# ESC_Board_Sample.net
KiCad netlist of a schematic drawn in Altium Designer
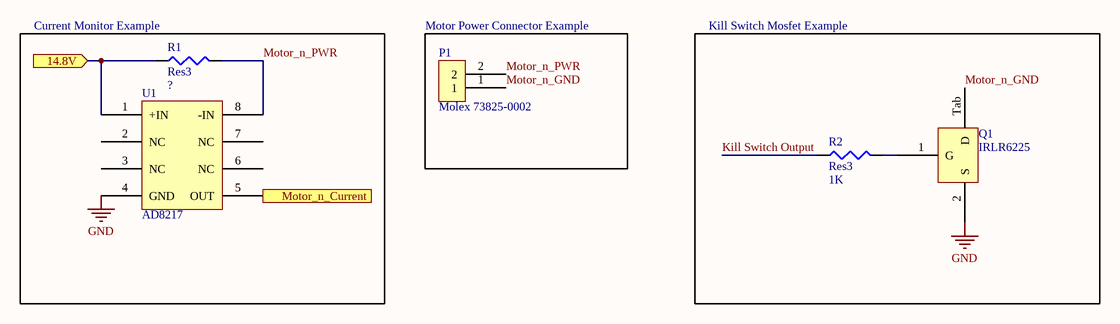
[diagram p0: ESC Board Sample.SchDoc]

(export (version "E")
  (design (tool "Eeschema 10.0.6"))
  (components
    (comp (ref "P1")
      (value "Molex 73825-0002")
      (footprint "Molex 76825-0002")
      (libsource (lib "Molex_Mega_Fit") (part "Molex 73825-0002"))
    )
    (comp (ref "Q1")
      (value "IRLR6225")
      (footprint "IRLR6225")
      (libsource (lib "BaseKillSwitchCircuit") (part "IRLR6225"))
    )
    (comp (ref "R1")
      (value "Res3")
      (footprint "J1-0603")
      (description "Resistor")
      (fields (field (name "ALTIUM_VALUE") "?") (field (name "PUBLISHER") "Altium Limited"))
      (libsource (lib "Miscellaneous Devices") (part "Res3"))
    )
    (comp (ref "R2")
      (value "Res3")
      (footprint "J1-0603")
      (description "Resistor")
      (fields (field (name "ALTIUM_VALUE") "1K") (field (name "PUBLISHER") "Altium Limited"))
      (libsource (lib "BaseKillSwitchCircuit") (part "Res3"))
    )
    (comp (ref "U1")
      (value "AD8217")
      (footprint "AD8217")
      (libsource (lib "BaseCurrentMonitor") (part "AD8217"))
    )
  )
  (nets
    (net (code "1") (name "/14.8V") (class "Default")
      (node (ref "R1") (pin "1") (pinfunction "1_1") (pintype "passive"))
      (node (ref "U1") (pin "1") (pinfunction "+IN_1") (pintype "passive"))
    )
    (net (code "2") (name "/Kill Switch Output") (class "Default")
      (node (ref "R2") (pin "1") (pinfunction "1_1") (pintype "passive"))
    )
    (net (code "3") (name "/Motor_n_Current") (class "Default")
      (node (ref "U1") (pin "5") (pinfunction "OUT_5") (pintype "passive"))
    )
    (net (code "4") (name "/Motor_n_GND") (class "Default")
      (node (ref "P1") (pin "1") (pinfunction "1_1") (pintype "power_in"))
      (node (ref "Q1") (pin "Tab") (pinfunction "D_Tab") (pintype "passive"))
    )
    (net (code "5") (name "/Motor_n_PWR") (class "Default")
      (node (ref "P1") (pin "2") (pinfunction "2_2") (pintype "power_in"))
      (node (ref "R1") (pin "2") (pinfunction "2_2") (pintype "passive"))
      (node (ref "U1") (pin "8") (pinfunction "-IN_8") (pintype "passive"))
    )
    (net (code "6") (name "GND") (class "Default")
      (node (ref "Q1") (pin "2") (pinfunction "S_2") (pintype "passive"))
      (node (ref "U1") (pin "4") (pinfunction "GND_4") (pintype "passive"))
    )
    (net (code "7") (name "Net-(Q1-G)") (class "Default")
      (node (ref "Q1") (pin "1") (pinfunction "G_1") (pintype "passive"))
      (node (ref "R2") (pin "2") (pinfunction "2_2") (pintype "passive"))
    )
    (net (code "8") (name "unconnected-(U1-NC-Pad2)") (class "Default")
      (node (ref "U1") (pin "2") (pinfunction "NC_2") (pintype "passive"))
    )
    (net (code "9") (name "unconnected-(U1-NC-Pad3)") (class "Default")
      (node (ref "U1") (pin "3") (pinfunction "NC_3") (pintype "passive"))
    )
    (net (code "10") (name "unconnected-(U1-NC-Pad6)") (class "Default")
      (node (ref "U1") (pin "6") (pinfunction "NC_6") (pintype "passive"))
    )
    (net (code "11") (name "unconnected-(U1-NC-Pad7)") (class "Default")
      (node (ref "U1") (pin "7") (pinfunction "NC_7") (pintype "passive"))
    )
  )
)
